# Sheet1.net
KiCad netlist of a schematic drawn in Altium Designer
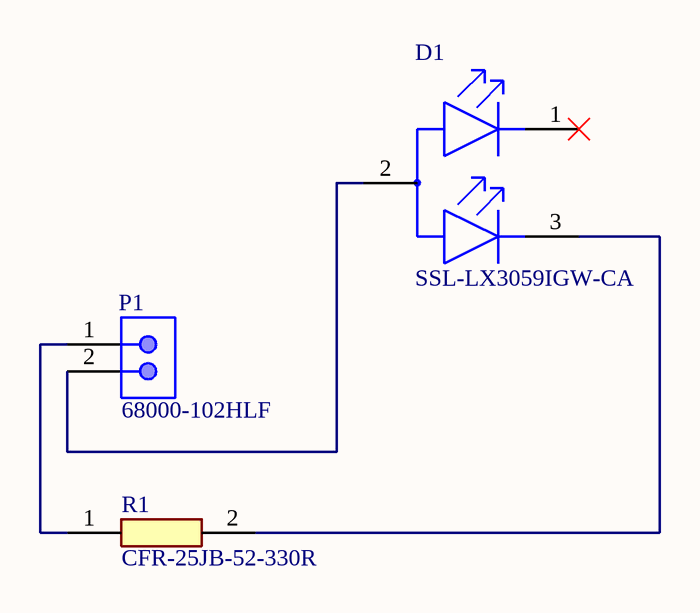
[diagram p0: Sheet1.SchDoc]

(export (version "E")
  (design (tool "Eeschema 10.0.6"))
  (components
    (comp (ref "D1")
      (value "SSL-LX3059IGW-CA")
      (footprint "FP-SSL-LX3059IGW-CA-MFG")
      (description "T-3MM BI-COLOR LED 635NM RED/")
      (libsource (lib "Altium Content Vault") (part "2322ea460f5524a061739ce0b58abb9"))
    )
    (comp (ref "P1")
      (value "68000-102HLF")
      (footprint "AMPH-68000-102HLF_V")
      (description "Male Header, Pitch 2.54 mm, 1 x 2 Position, Height 8.38 mm, Tail Length 2.41 mm, RoHS, Bulk")
      (fields (field (name "MANUFACTURER") "FCI"))
      (libsource (lib "Altium Content Vault") (part "CN-1P-M-R2"))
    )
    (comp (ref "R1")
      (value "CFR-25JB-52-330R")
      (footprint "SamacSys:RESAD1590W60L630D240")
      (description "Resistor")
      (fields (field (name "MOUSER PART NUMBER") "603-CFR-25JB-52-330R"))
      (libsource (lib "*") (part "CFR-25JB-52-330R"))
    )
  )
  (nets
    (net (code "1") (name "Net-(D1-COMMON_ANODE)") (class "Default")
      (node (ref "D1") (pin "2") (pinfunction "COMMON_ANODE_2") (pintype "passive"))
      (node (ref "P1") (pin "2") (pinfunction "2_2") (pintype "passive"))
    )
    (net (code "2") (name "Net-(D1-GREEN_C)") (class "Default")
      (node (ref "D1") (pin "3") (pinfunction "GREEN_C_3") (pintype "passive"))
      (node (ref "R1") (pin "2") (pinfunction "2_2") (pintype "passive"))
    )
    (net (code "3") (name "Net-(P1-Pad1)") (class "Default")
      (node (ref "P1") (pin "1") (pinfunction "1_1") (pintype "passive"))
      (node (ref "R1") (pin "1") (pinfunction "1_1") (pintype "passive"))
    )
    (net (code "4") (name "unconnected-(D1-RED_C-Pad1)") (class "Default")
      (node (ref "D1") (pin "1") (pinfunction "RED_C_1") (pintype "passive+no_connect"))
    )
  )
)
